# itsy_bitsy_to_pro_micro.net
KiCad netlist of a schematic drawn in EAGLE
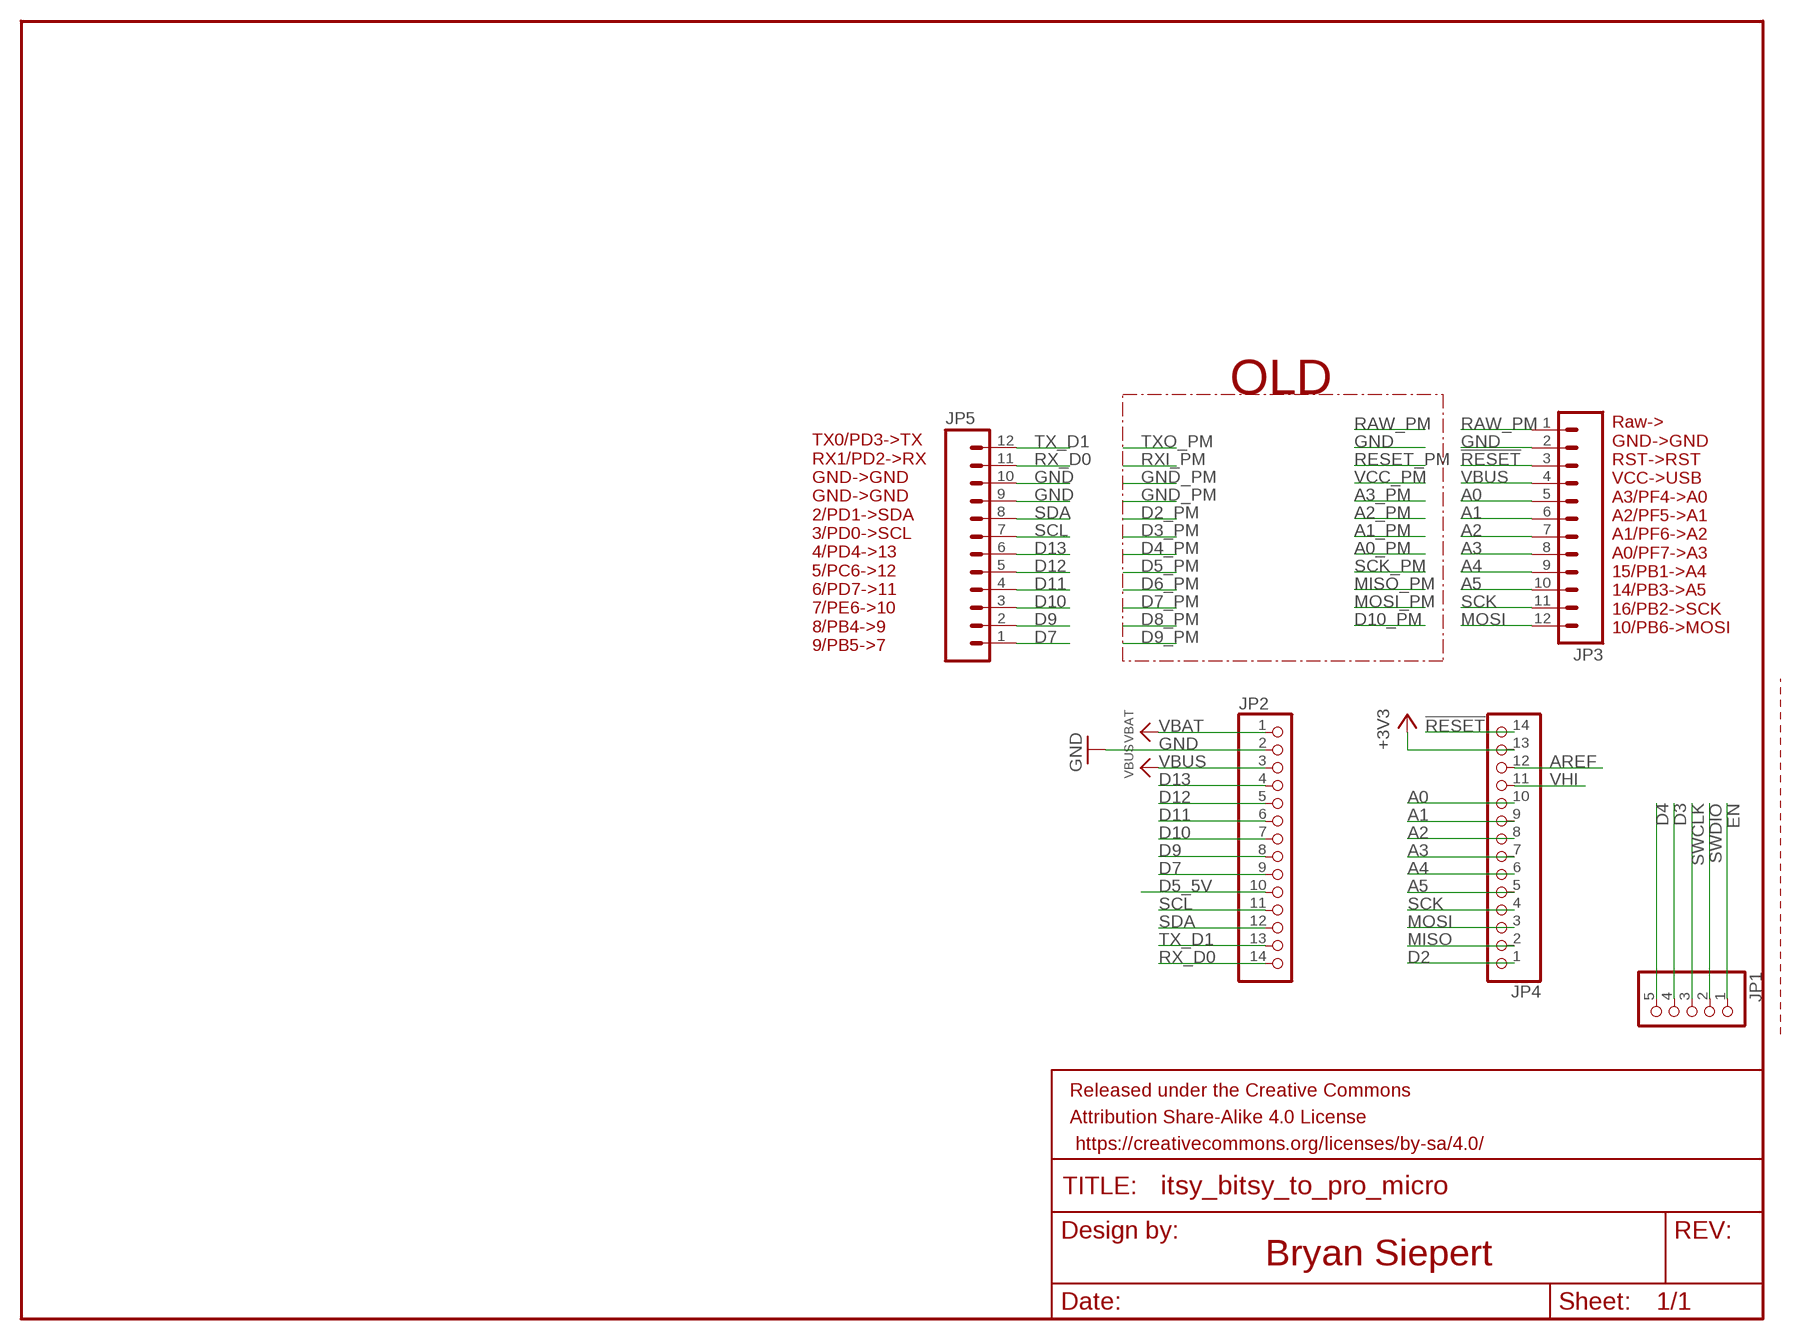
[diagram p0: schematic, sheet 1]

(export (version "E")
  (design (tool "Eeschema 10.0.6"))
  (components
    (comp (ref "FRAME2")
      (value "FRAME-LETTER")
      (footprint "eagle-import:CREATIVE_COMMONS")
      (libsource (lib "eagle-import") (part "FRAME-LETTER"))
    )
    (comp (ref "JP1")
      (value "HEADER-1X570MIL")
      (footprint "eagle-import:1X05_ROUND_70")
      (libsource (lib "eagle-import") (part "HEADER-1X570MIL"))
    )
    (comp (ref "JP2")
      (value "HEADER-1X14")
      (footprint "eagle-import:1X14_ROUND70")
      (libsource (lib "eagle-import") (part "HEADER-1X14"))
    )
    (comp (ref "JP3")
      (value "M12PTH")
      (footprint "eagle-import:1X12")
      (libsource (lib "eagle-import") (part "M12PTH"))
    )
    (comp (ref "JP4")
      (value "HEADER-1X14")
      (footprint "eagle-import:1X14_ROUND70")
      (libsource (lib "eagle-import") (part "HEADER-1X14"))
    )
    (comp (ref "JP5")
      (value "M12PTH")
      (footprint "eagle-import:1X12")
      (libsource (lib "eagle-import") (part "M12PTH"))
    )
  )
  (nets
    (net (code "1") (name "+3V3") (class "Default")
      (node (ref "JP4") (pin "13") (pinfunction "13_13") (pintype "passive"))
    )
    (net (code "2") (name "/A0") (class "Default")
      (node (ref "JP3") (pin "5") (pinfunction "5_5") (pintype "passive"))
      (node (ref "JP4") (pin "10") (pinfunction "10_10") (pintype "passive"))
    )
    (net (code "4") (name "/A1") (class "Default")
      (node (ref "JP3") (pin "6") (pinfunction "6_6") (pintype "passive"))
      (node (ref "JP4") (pin "9") (pinfunction "9_9") (pintype "passive"))
    )
    (net (code "6") (name "/A2") (class "Default")
      (node (ref "JP3") (pin "7") (pinfunction "7_7") (pintype "passive"))
      (node (ref "JP4") (pin "8") (pinfunction "8_8") (pintype "passive"))
    )
    (net (code "8") (name "/A3") (class "Default")
      (node (ref "JP3") (pin "8") (pinfunction "8_8") (pintype "passive"))
      (node (ref "JP4") (pin "7") (pinfunction "7_7") (pintype "passive"))
    )
    (net (code "10") (name "/A4") (class "Default")
      (node (ref "JP3") (pin "9") (pinfunction "9_9") (pintype "passive"))
      (node (ref "JP4") (pin "6") (pinfunction "6_6") (pintype "passive"))
    )
    (net (code "11") (name "/A5") (class "Default")
      (node (ref "JP3") (pin "10") (pinfunction "10_10") (pintype "passive"))
      (node (ref "JP4") (pin "5") (pinfunction "5_5") (pintype "passive"))
    )
    (net (code "12") (name "/AREF") (class "Default")
      (node (ref "JP4") (pin "12") (pinfunction "12_12") (pintype "passive"))
    )
    (net (code "13") (name "/D2") (class "Default")
      (node (ref "JP4") (pin "1") (pinfunction "1_1") (pintype "passive"))
    )
    (net (code "15") (name "/D3") (class "Default")
      (node (ref "JP1") (pin "4") (pinfunction "4_4") (pintype "passive"))
    )
    (net (code "17") (name "/D4") (class "Default")
      (node (ref "JP1") (pin "5") (pinfunction "5_5") (pintype "passive"))
    )
    (net (code "19") (name "/D5_5V") (class "Default")
      (node (ref "JP2") (pin "10") (pinfunction "10_10") (pintype "passive"))
    )
    (net (code "22") (name "/D7") (class "Default")
      (node (ref "JP2") (pin "9") (pinfunction "9_9") (pintype "passive"))
      (node (ref "JP5") (pin "1") (pinfunction "1_1") (pintype "passive"))
    )
    (net (code "25") (name "/D9") (class "Default")
      (node (ref "JP2") (pin "8") (pinfunction "8_8") (pintype "passive"))
      (node (ref "JP5") (pin "2") (pinfunction "2_2") (pintype "passive"))
    )
    (net (code "27") (name "/D10") (class "Default")
      (node (ref "JP2") (pin "7") (pinfunction "7_7") (pintype "passive"))
      (node (ref "JP5") (pin "3") (pinfunction "3_3") (pintype "passive"))
    )
    (net (code "29") (name "/D11") (class "Default")
      (node (ref "JP2") (pin "6") (pinfunction "6_6") (pintype "passive"))
      (node (ref "JP5") (pin "4") (pinfunction "4_4") (pintype "passive"))
    )
    (net (code "30") (name "/D12") (class "Default")
      (node (ref "JP2") (pin "5") (pinfunction "5_5") (pintype "passive"))
      (node (ref "JP5") (pin "5") (pinfunction "5_5") (pintype "passive"))
    )
    (net (code "31") (name "/D13") (class "Default")
      (node (ref "JP2") (pin "4") (pinfunction "4_4") (pintype "passive"))
      (node (ref "JP5") (pin "6") (pinfunction "6_6") (pintype "passive"))
    )
    (net (code "32") (name "/EN") (class "Default")
      (node (ref "JP1") (pin "1") (pinfunction "1_1") (pintype "passive"))
    )
    (net (code "34") (name "/MISO") (class "Default")
      (node (ref "JP4") (pin "2") (pinfunction "2_2") (pintype "passive"))
    )
    (net (code "36") (name "/MOSI") (class "Default")
      (node (ref "JP3") (pin "12") (pinfunction "12_12") (pintype "passive"))
      (node (ref "JP4") (pin "3") (pinfunction "3_3") (pintype "passive"))
    )
    (net (code "38") (name "/RAW_PM") (class "Default")
      (node (ref "JP3") (pin "1") (pinfunction "1_1") (pintype "passive"))
    )
    (net (code "41") (name "/RX_D0") (class "Default")
      (node (ref "JP2") (pin "14") (pinfunction "14_14") (pintype "passive"))
      (node (ref "JP5") (pin "11") (pinfunction "11_11") (pintype "passive"))
    )
    (net (code "42") (name "/SCK") (class "Default")
      (node (ref "JP3") (pin "11") (pinfunction "11_11") (pintype "passive"))
      (node (ref "JP4") (pin "4") (pinfunction "4_4") (pintype "passive"))
    )
    (net (code "44") (name "/SCL") (class "Default")
      (node (ref "JP2") (pin "11") (pinfunction "11_11") (pintype "passive"))
      (node (ref "JP5") (pin "7") (pinfunction "7_7") (pintype "passive"))
    )
    (net (code "45") (name "/SDA") (class "Default")
      (node (ref "JP2") (pin "12") (pinfunction "12_12") (pintype "passive"))
      (node (ref "JP5") (pin "8") (pinfunction "8_8") (pintype "passive"))
    )
    (net (code "46") (name "/SWCLK") (class "Default")
      (node (ref "JP1") (pin "3") (pinfunction "3_3") (pintype "passive"))
    )
    (net (code "47") (name "/SWDIO") (class "Default")
      (node (ref "JP1") (pin "2") (pinfunction "2_2") (pintype "passive"))
    )
    (net (code "49") (name "/TX_D1") (class "Default")
      (node (ref "JP2") (pin "13") (pinfunction "13_13") (pintype "passive"))
      (node (ref "JP5") (pin "12") (pinfunction "12_12") (pintype "passive"))
    )
    (net (code "51") (name "/VHI") (class "Default")
      (node (ref "JP4") (pin "11") (pinfunction "11_11") (pintype "passive"))
    )
    (net (code "52") (name "/~{RESET}") (class "Default")
      (node (ref "JP3") (pin "3") (pinfunction "3_3") (pintype "passive"))
      (node (ref "JP4") (pin "14") (pinfunction "14_14") (pintype "passive"))
    )
    (net (code "53") (name "GND") (class "Default")
      (node (ref "JP2") (pin "2") (pinfunction "2_2") (pintype "passive"))
      (node (ref "JP3") (pin "2") (pinfunction "2_2") (pintype "passive"))
      (node (ref "JP5") (pin "10") (pinfunction "10_10") (pintype "passive"))
      (node (ref "JP5") (pin "9") (pinfunction "9_9") (pintype "passive"))
    )
    (net (code "54") (name "VBAT") (class "Default")
      (node (ref "JP2") (pin "1") (pinfunction "1_1") (pintype "passive"))
    )
    (net (code "55") (name "VBUS") (class "Default")
      (node (ref "JP2") (pin "3") (pinfunction "3_3") (pintype "passive"))
      (node (ref "JP3") (pin "4") (pinfunction "4_4") (pintype "passive"))
    )
  )
)
